# Pro_Micro_582V0_1.net
KiCad netlist of a schematic drawn in Altium Designer
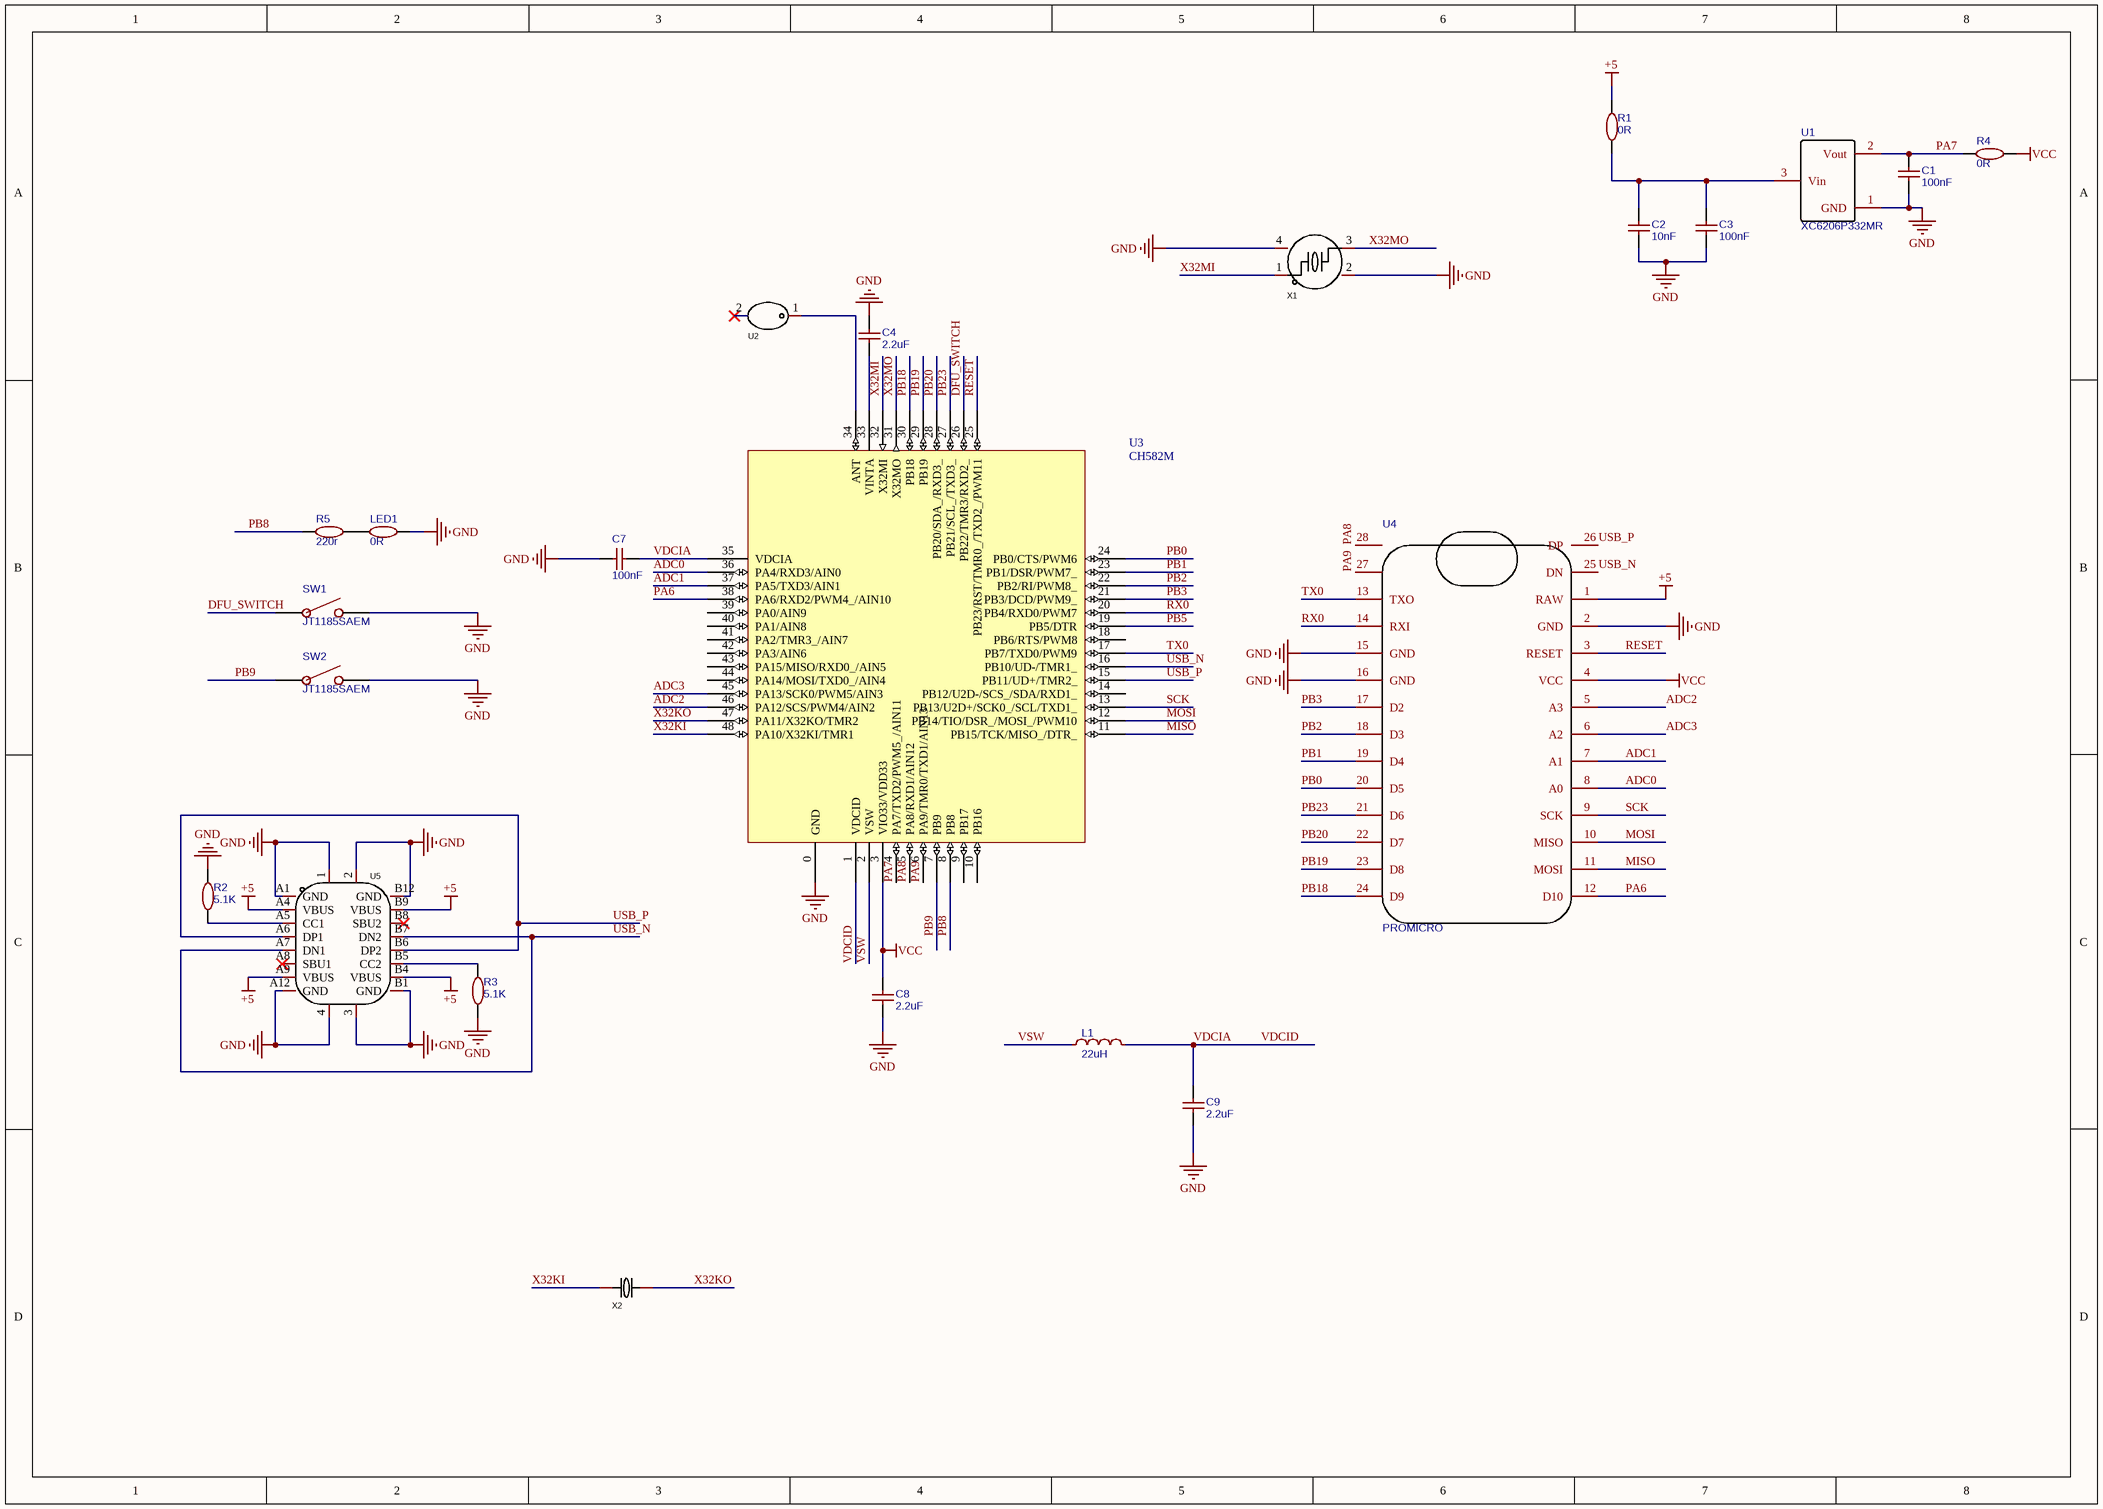
[diagram p0: Pro_Micro_582V0.1.SchDoc]

(export (version "E")
  (design (tool "Eeschema 10.0.6"))
  (components
    (comp (ref "C1")
      (value "100nF")
      (footprint "C0402")
      (fields
        (field (name "BOM_MANUFACTURER PART") "CC0805KKX5R6BB106")
        (field (name "BOM_SUPPLIER PART") "C89832")
      )
      (libsource (lib "CH582M") (part "电容"))
    )
    (comp (ref "C2")
      (value "10nF")
      (footprint "C0402")
      (fields
        (field (name "BOM_MANUFACTURER PART") "CC0805KKX5R6BB106")
        (field (name "BOM_SUPPLIER PART") "C89832")
      )
      (libsource (lib "CH582M") (part "电容"))
    )
    (comp (ref "C3")
      (value "100nF")
      (footprint "C0402")
      (fields
        (field (name "BOM_MANUFACTURER PART") "CC0805KKX5R6BB106")
        (field (name "BOM_SUPPLIER PART") "C89832")
      )
      (libsource (lib "CH582M") (part "电容"))
    )
    (comp (ref "C4")
      (value "2.2uF")
      (footprint "C0402")
      (fields
        (field (name "BOM_MANUFACTURER PART") "CC0805KKX5R6BB106")
        (field (name "BOM_SUPPLIER PART") "C89832")
      )
      (libsource (lib "CH582M") (part "电容"))
    )
    (comp (ref "C7")
      (value "100nF")
      (footprint "C0402")
      (fields
        (field (name "BOM_MANUFACTURER PART") "CC0805KKX5R6BB106")
        (field (name "BOM_SUPPLIER PART") "C89832")
      )
      (libsource (lib "CH582M") (part "电容"))
    )
    (comp (ref "C8")
      (value "2.2uF")
      (footprint "C0402")
      (fields
        (field (name "BOM_MANUFACTURER PART") "CC0805KKX5R6BB106")
        (field (name "BOM_SUPPLIER PART") "C89832")
      )
      (libsource (lib "CH582M") (part "电容"))
    )
    (comp (ref "C9")
      (value "2.2uF")
      (footprint "C0402")
      (fields
        (field (name "BOM_MANUFACTURER PART") "CC0805KKX5R6BB106")
        (field (name "BOM_SUPPLIER PART") "C89832")
      )
      (libsource (lib "CH582M") (part "电容"))
    )
    (comp (ref "L1")
      (value "22uH")
      (footprint "L0805")
      (fields
        (field (name "BOM_SUPPLIER PART") "C223184")
        (field (name "BOM_MANUFACTURER PART") "CBC2012T220K")
        (field (name "CONTRIBUTOR") "LCSC")
      )
      (libsource (lib "CH582M") (part "22uH"))
    )
    (comp (ref "LED1")
      (value "0R")
      (footprint "C0402")
      (fields
        (field (name "BOM_MANUFACTURER PART") "0603WAF1002T5E")
        (field (name "BOM_SUPPLIER PART") "C25804")
      )
      (libsource (lib "CH582M") (part "电阻"))
    )
    (comp (ref "R1")
      (value "0R")
      (footprint "R0402")
      (fields
        (field (name "BOM_MANUFACTURER PART") "0603WAF1002T5E")
        (field (name "BOM_SUPPLIER PART") "C25804")
      )
      (libsource (lib "CH582M") (part "电阻"))
    )
    (comp (ref "R2")
      (value "5.1K")
      (footprint "R0402")
      (fields
        (field (name "BOM_MANUFACTURER PART") "0603WAF1002T5E")
        (field (name "BOM_SUPPLIER PART") "C25804")
      )
      (libsource (lib "CH582M") (part "电阻"))
    )
    (comp (ref "R3")
      (value "5.1K")
      (footprint "R0402")
      (fields
        (field (name "BOM_MANUFACTURER PART") "0603WAF1002T5E")
        (field (name "BOM_SUPPLIER PART") "C25804")
      )
      (libsource (lib "CH582M") (part "电阻"))
    )
    (comp (ref "R4")
      (value "0R")
      (footprint "R0402")
      (fields
        (field (name "BOM_MANUFACTURER PART") "0603WAF1002T5E")
        (field (name "BOM_SUPPLIER PART") "C25804")
      )
      (libsource (lib "CH582M") (part "电阻"))
    )
    (comp (ref "R5")
      (value "220r")
      (footprint "C0402")
      (fields
        (field (name "BOM_MANUFACTURER PART") "0603WAF1002T5E")
        (field (name "BOM_SUPPLIER PART") "C25804")
      )
      (libsource (lib "CH582M") (part "电阻"))
    )
    (comp (ref "SW1")
      (value "JT1185SAEM")
      (footprint "SW-SMD_L3.9-W2.9-P4.15-LS5.0")
      (fields (field (name "BOM_SUPPLIER PART") "C465068") (field (name "CONTRIBUTOR") "LCSC"))
      (libsource (lib "CH582M") (part "JT1185SAEM"))
    )
    (comp (ref "SW2")
      (value "JT1185SAEM")
      (footprint "SW-SMD_L3.9-W2.9-P4.15-LS5.0")
      (fields (field (name "BOM_SUPPLIER PART") "C465068") (field (name "CONTRIBUTOR") "LCSC"))
      (libsource (lib "CH582M") (part "JT1185SAEM"))
    )
    (comp (ref "U1")
      (value "XC6206P332MR")
      (footprint "SOT-23-3_L2.9-W1.6-P1.90-LS2.8-BR")
      (fields (field (name "BOM_SUPPLIER PART") "C5446"))
      (libsource (lib "M2参考") (part "XC6206P332MR"))
    )
    (comp (ref "U2")
      (value "RFANT3216120A5T")
      (footprint "FILTER-SMD_1206-2P-L3.2-W1.6-L")
      (fields (field (name "MANUFACTURER") "Walsin(华新科)"))
      (libsource (lib "CH582M") (part "RFANT3216120A5T"))
    )
    (comp (ref "U3")
      (value "CH582M")
      (footprint "QFN48_5X5")
      (description "RISC-V MCU with BLE/2*USB/ADC/PWM/SPI/I2C/4*UART")
      (libsource (lib "CHXXX") (part "CH582M"))
    )
    (comp (ref "U4")
      (value "PROMICRO")
      (footprint "PROMICRO邮票孔")
      (fields (field (name "CONTRIBUTOR") "KongC"))
      (libsource (lib "Pro_Micro_CH582M") (part "PROMICRO"))
    )
    (comp (ref "U5")
      (value "20009-UCAF001-X")
      (footprint "TYPE-C-SMD_20009-UCAF001-X")
      (fields (field (name "MANUFACTURER") "MINTRON(明硕)"))
      (libsource (lib "CH582M") (part "20009-UCAF001-X"))
    )
    (comp (ref "X1")
      (value "X201632MOB4SI")
      (footprint "CRYSTAL-SMD_4P-L2.0-W1.6-BL-2")
      (fields (field (name "MANUFACTURER") "YXC(扬兴晶振)"))
      (libsource (lib "CH582M") (part "X201632MOB4SI"))
    )
    (comp (ref "X2")
      (value "SC-32S32.768kHz20PPM12.5pF")
      (footprint "OSC-SMD_L3.2-W1.5")
      (fields (field (name "MANUFACTURER") "Seiko(精工)"))
      (libsource (lib "CH582M") (part "SC-32S32.768kHz20PPM12.5pF"))
    )
  )
  (nets
    (net (code "1") (name "+5") (class "Default")
      (node (ref "R1") (pin "2") (pinfunction "2_2") (pintype "passive"))
      (node (ref "U4") (pin "1") (pinfunction "RAW_1") (pintype "passive"))
      (node (ref "U5") (pin "A4") (pinfunction "VBUS_A4") (pintype "passive"))
      (node (ref "U5") (pin "A9") (pinfunction "VBUS_A9") (pintype "passive"))
      (node (ref "U5") (pin "B4") (pinfunction "VBUS_B4") (pintype "passive"))
      (node (ref "U5") (pin "B9") (pinfunction "VBUS_B9") (pintype "passive"))
    )
    (net (code "2") (name "/ADC0") (class "Default")
      (node (ref "U3") (pin "36") (pinfunction "PA4/RXD3/AIN0_36") (pintype "bidirectional"))
      (node (ref "U4") (pin "8") (pinfunction "A0_8") (pintype "passive"))
    )
    (net (code "3") (name "/ADC1") (class "Default")
      (node (ref "U3") (pin "37") (pinfunction "PA5/TXD3/AIN1_37") (pintype "bidirectional"))
      (node (ref "U4") (pin "7") (pinfunction "A1_7") (pintype "passive"))
    )
    (net (code "4") (name "/ADC2") (class "Default")
      (node (ref "U3") (pin "46") (pinfunction "PA12/SCS/PWM4/AIN2_46") (pintype "bidirectional"))
      (node (ref "U4") (pin "5") (pinfunction "A3_5") (pintype "passive"))
    )
    (net (code "5") (name "/ADC3") (class "Default")
      (node (ref "U3") (pin "45") (pinfunction "PA13/SCK0/PWM5/AIN3_45") (pintype "bidirectional"))
      (node (ref "U4") (pin "6") (pinfunction "A2_6") (pintype "passive"))
    )
    (net (code "6") (name "/DFU_SWITCH") (class "Default")
      (node (ref "SW1") (pin "1") (pinfunction "1_1") (pintype "passive"))
      (node (ref "U3") (pin "26") (pinfunction "PB22/TMR3/RXD2__26") (pintype "bidirectional"))
    )
    (net (code "7") (name "/MISO") (class "Default")
      (node (ref "U3") (pin "11") (pinfunction "PB15/TCK/MISO_/DTR__11") (pintype "bidirectional"))
      (node (ref "U4") (pin "11") (pinfunction "MOSI_11") (pintype "passive"))
    )
    (net (code "8") (name "/MOSI") (class "Default")
      (node (ref "U3") (pin "12") (pinfunction "PB14/TIO/DSR_/MOSI_/PWM10_12") (pintype "bidirectional"))
      (node (ref "U4") (pin "10") (pinfunction "MISO_10") (pintype "passive"))
    )
    (net (code "9") (name "/PA6") (class "Default")
      (node (ref "U3") (pin "38") (pinfunction "PA6/RXD2/PWM4_/AIN10_38") (pintype "bidirectional"))
      (node (ref "U4") (pin "12") (pinfunction "D10_12") (pintype "passive"))
    )
    (net (code "10") (name "/PA7") (class "Default")
      (node (ref "C1") (pin "2") (pinfunction "2_2") (pintype "passive"))
      (node (ref "R4") (pin "2") (pinfunction "2_2") (pintype "passive"))
      (node (ref "U1") (pin "2") (pinfunction "Vout_2") (pintype "passive"))
      (node (ref "U3") (pin "4") (pinfunction "PA7/TXD2/PWM5_/AIN11_4") (pintype "bidirectional"))
    )
    (net (code "11") (name "/PA8") (class "Default")
      (node (ref "U3") (pin "5") (pinfunction "PA8/RXD1/AIN12_5") (pintype "bidirectional"))
      (node (ref "U4") (pin "28") (pintype "passive"))
    )
    (net (code "12") (name "/PA9") (class "Default")
      (node (ref "U3") (pin "6") (pinfunction "PA9/TMR0/TXD1/AIN13_6") (pintype "bidirectional"))
      (node (ref "U4") (pin "27") (pintype "passive"))
    )
    (net (code "13") (name "/PB0") (class "Default")
      (node (ref "U3") (pin "24") (pinfunction "PB0/CTS/PWM6_24") (pintype "bidirectional"))
      (node (ref "U4") (pin "20") (pinfunction "D5_20") (pintype "passive"))
    )
    (net (code "14") (name "/PB1") (class "Default")
      (node (ref "U3") (pin "23") (pinfunction "PB1/DSR/PWM7__23") (pintype "bidirectional"))
      (node (ref "U4") (pin "19") (pinfunction "D4_19") (pintype "passive"))
    )
    (net (code "15") (name "/PB2") (class "Default")
      (node (ref "U3") (pin "22") (pinfunction "PB2/RI/PWM8__22") (pintype "bidirectional"))
      (node (ref "U4") (pin "18") (pinfunction "D3_18") (pintype "passive"))
    )
    (net (code "16") (name "/PB3") (class "Default")
      (node (ref "U3") (pin "21") (pinfunction "PB3/DCD/PWM9__21") (pintype "bidirectional"))
      (node (ref "U4") (pin "17") (pinfunction "D2_17") (pintype "passive"))
    )
    (net (code "17") (name "/PB5") (class "Default")
      (node (ref "U3") (pin "19") (pinfunction "PB5/DTR_19") (pintype "bidirectional"))
    )
    (net (code "18") (name "/PB8") (class "Default")
      (node (ref "R5") (pin "1") (pinfunction "1_1") (pintype "passive"))
      (node (ref "U3") (pin "8") (pinfunction "PB8_8") (pintype "bidirectional"))
    )
    (net (code "19") (name "/PB9") (class "Default")
      (node (ref "SW2") (pin "1") (pinfunction "1_1") (pintype "passive"))
      (node (ref "U3") (pin "7") (pinfunction "PB9_7") (pintype "bidirectional"))
    )
    (net (code "20") (name "/PB18") (class "Default")
      (node (ref "U3") (pin "30") (pinfunction "PB18_30") (pintype "bidirectional"))
      (node (ref "U4") (pin "24") (pinfunction "D9_24") (pintype "passive"))
    )
    (net (code "21") (name "/PB19") (class "Default")
      (node (ref "U3") (pin "29") (pinfunction "PB19_29") (pintype "bidirectional"))
      (node (ref "U4") (pin "23") (pinfunction "D8_23") (pintype "passive"))
    )
    (net (code "22") (name "/PB20") (class "Default")
      (node (ref "U3") (pin "28") (pinfunction "PB20/SDA_/RXD3__28") (pintype "bidirectional"))
      (node (ref "U4") (pin "22") (pinfunction "D7_22") (pintype "passive"))
    )
    (net (code "23") (name "/PB23") (class "Default")
      (node (ref "U3") (pin "27") (pinfunction "PB21/SCL_/TXD3__27") (pintype "bidirectional"))
      (node (ref "U4") (pin "21") (pinfunction "D6_21") (pintype "passive"))
    )
    (net (code "24") (name "/RESET") (class "Default")
      (node (ref "U3") (pin "25") (pinfunction "PB23/RST/TMR0_/TXD2_/PWM11_25") (pintype "bidirectional"))
      (node (ref "U4") (pin "3") (pinfunction "RESET_3") (pintype "passive"))
    )
    (net (code "25") (name "/RX0") (class "Default")
      (node (ref "U3") (pin "20") (pinfunction "PB4/RXD0/PWM7_20") (pintype "bidirectional"))
      (node (ref "U4") (pin "14") (pinfunction "RXI_14") (pintype "passive"))
    )
    (net (code "26") (name "/SCK") (class "Default")
      (node (ref "U3") (pin "13") (pinfunction "PB13/U2D+/SCK0_/SCL/TXD1__13") (pintype "bidirectional"))
      (node (ref "U4") (pin "9") (pinfunction "SCK_9") (pintype "passive"))
    )
    (net (code "27") (name "/TX0") (class "Default")
      (node (ref "U3") (pin "17") (pinfunction "PB7/TXD0/PWM9_17") (pintype "bidirectional"))
      (node (ref "U4") (pin "13") (pinfunction "TXO_13") (pintype "passive"))
    )
    (net (code "28") (name "/USB_N") (class "Default")
      (node (ref "U3") (pin "16") (pinfunction "PB10/UD-/TMR1__16") (pintype "bidirectional"))
      (node (ref "U4") (pin "25") (pinfunction "DN_25") (pintype "passive"))
      (node (ref "U5") (pin "A7") (pinfunction "DN1_A7") (pintype "passive"))
      (node (ref "U5") (pin "B7") (pinfunction "DN2_B7") (pintype "passive"))
    )
    (net (code "29") (name "/USB_P") (class "Default")
      (node (ref "U3") (pin "15") (pinfunction "PB11/UD+/TMR2__15") (pintype "bidirectional"))
      (node (ref "U4") (pin "26") (pinfunction "DP_26") (pintype "passive"))
      (node (ref "U5") (pin "A6") (pinfunction "DP1_A6") (pintype "passive"))
      (node (ref "U5") (pin "B6") (pinfunction "DP2_B6") (pintype "passive"))
    )
    (net (code "30") (name "/VDCIA") (class "Default")
      (node (ref "C7") (pin "1") (pinfunction "1_1") (pintype "passive"))
      (node (ref "C9") (pin "2") (pinfunction "2_2") (pintype "passive"))
      (node (ref "L1") (pin "2") (pinfunction "2_2") (pintype "passive"))
      (node (ref "U3") (pin "1") (pinfunction "VDCID_1") (pintype "power_in"))
      (node (ref "U3") (pin "35") (pinfunction "VDCIA_35") (pintype "power_in"))
    )
    (net (code "31") (name "/VSW") (class "Default")
      (node (ref "L1") (pin "1") (pinfunction "1_1") (pintype "passive"))
      (node (ref "U3") (pin "2") (pinfunction "VSW_2") (pintype "power_in"))
    )
    (net (code "32") (name "/X32KI") (class "Default")
      (node (ref "U3") (pin "48") (pinfunction "PA10/X32KI/TMR1_48") (pintype "bidirectional"))
      (node (ref "X2") (pin "1") (pinfunction "1_1") (pintype "passive"))
    )
    (net (code "33") (name "/X32KO") (class "Default")
      (node (ref "U3") (pin "47") (pinfunction "PA11/X32KO/TMR2_47") (pintype "bidirectional"))
      (node (ref "X2") (pin "2") (pinfunction "2_2") (pintype "passive"))
    )
    (net (code "34") (name "/X32MI") (class "Default")
      (node (ref "U3") (pin "32") (pinfunction "X32MI_32") (pintype "input"))
      (node (ref "X1") (pin "1") (pinfunction "1_1") (pintype "passive"))
    )
    (net (code "35") (name "/X32MO") (class "Default")
      (node (ref "U3") (pin "31") (pinfunction "X32MO_31") (pintype "output"))
      (node (ref "X1") (pin "3") (pinfunction "3_3") (pintype "passive"))
    )
    (net (code "36") (name "GND") (class "Default")
      (node (ref "C1") (pin "1") (pinfunction "1_1") (pintype "passive"))
      (node (ref "C2") (pin "1") (pinfunction "1_1") (pintype "passive"))
      (node (ref "C3") (pin "1") (pinfunction "1_1") (pintype "passive"))
      (node (ref "C4") (pin "2") (pinfunction "2_2") (pintype "passive"))
      (node (ref "C7") (pin "2") (pinfunction "2_2") (pintype "passive"))
      (node (ref "C8") (pin "1") (pinfunction "1_1") (pintype "passive"))
      (node (ref "C9") (pin "1") (pinfunction "1_1") (pintype "passive"))
      (node (ref "LED1") (pin "1") (pinfunction "1_1") (pintype "passive"))
      (node (ref "R2") (pin "2") (pinfunction "2_2") (pintype "passive"))
      (node (ref "R3") (pin "2") (pinfunction "2_2") (pintype "passive"))
      (node (ref "SW1") (pin "2") (pinfunction "2_2") (pintype "passive"))
      (node (ref "SW2") (pin "2") (pinfunction "2_2") (pintype "passive"))
      (node (ref "U1") (pin "1") (pinfunction "GND_1") (pintype "passive"))
      (node (ref "U3") (pin "0") (pinfunction "GND_0") (pintype "power_in"))
      (node (ref "U4") (pin "15") (pinfunction "GND_15") (pintype "passive"))
      (node (ref "U4") (pin "16") (pinfunction "GND_16") (pintype "passive"))
      (node (ref "U4") (pin "2") (pinfunction "GND_2") (pintype "passive"))
      (node (ref "U5") (pin "1") (pinfunction "1_1") (pintype "passive"))
      (node (ref "U5") (pin "2") (pinfunction "2_2") (pintype "passive"))
      (node (ref "U5") (pin "3") (pinfunction "3_3") (pintype "passive"))
      (node (ref "U5") (pin "4") (pinfunction "4_4") (pintype "passive"))
      (node (ref "U5") (pin "A1") (pinfunction "GND_A1") (pintype "passive"))
      (node (ref "U5") (pin "A12") (pinfunction "GND_A12") (pintype "passive"))
      (node (ref "U5") (pin "B1") (pinfunction "GND_B1") (pintype "passive"))
      (node (ref "U5") (pin "B12") (pinfunction "GND_B12") (pintype "passive"))
      (node (ref "X1") (pin "2") (pinfunction "GND_2") (pintype "passive"))
      (node (ref "X1") (pin "4") (pinfunction "GND_4") (pintype "passive"))
    )
    (net (code "37") (name "Net-(LED1-Pad2)") (class "Default")
      (node (ref "LED1") (pin "2") (pinfunction "2_2") (pintype "passive"))
      (node (ref "R5") (pin "2") (pinfunction "2_2") (pintype "passive"))
    )
    (net (code "38") (name "Net-(U1-Vin)") (class "Default")
      (node (ref "C2") (pin "2") (pinfunction "2_2") (pintype "passive"))
      (node (ref "C3") (pin "2") (pinfunction "2_2") (pintype "passive"))
      (node (ref "R1") (pin "1") (pinfunction "1_1") (pintype "passive"))
      (node (ref "U1") (pin "3") (pinfunction "Vin_3") (pintype "passive"))
    )
    (net (code "39") (name "Net-(U3-ANT)") (class "Default")
      (node (ref "U2") (pin "1") (pinfunction "1_1") (pintype "passive"))
      (node (ref "U3") (pin "34") (pinfunction "ANT_34") (pintype "bidirectional"))
    )
    (net (code "40") (name "Net-(U3-VINTA)") (class "Default")
      (node (ref "C4") (pin "1") (pinfunction "1_1") (pintype "passive"))
      (node (ref "U3") (pin "33") (pinfunction "VINTA_33") (pintype "power_in"))
    )
    (net (code "41") (name "Net-(U5-CC1)") (class "Default")
      (node (ref "R2") (pin "1") (pinfunction "1_1") (pintype "passive"))
      (node (ref "U5") (pin "A5") (pinfunction "CC1_A5") (pintype "passive"))
    )
    (net (code "42") (name "Net-(U5-CC2)") (class "Default")
      (node (ref "R3") (pin "1") (pinfunction "1_1") (pintype "passive"))
      (node (ref "U5") (pin "B5") (pinfunction "CC2_B5") (pintype "passive"))
    )
    (net (code "43") (name "VCC") (class "Default")
      (node (ref "C8") (pin "2") (pinfunction "2_2") (pintype "passive"))
      (node (ref "R4") (pin "1") (pinfunction "1_1") (pintype "passive"))
      (node (ref "U3") (pin "3") (pinfunction "VIO33/VDD33_3") (pintype "power_in"))
      (node (ref "U4") (pin "4") (pinfunction "VCC_4") (pintype "passive"))
    )
    (net (code "44") (name "unconnected-(U2-Pad2)") (class "Default")
      (node (ref "U2") (pin "2") (pinfunction "2_2") (pintype "passive+no_connect"))
    )
    (net (code "45") (name "unconnected-(U3-PA0{slash}AIN9-Pad39)") (class "Default")
      (node (ref "U3") (pin "39") (pinfunction "PA0/AIN9_39") (pintype "bidirectional"))
    )
    (net (code "46") (name "unconnected-(U3-PA1{slash}AIN8-Pad40)") (class "Default")
      (node (ref "U3") (pin "40") (pinfunction "PA1/AIN8_40") (pintype "bidirectional"))
    )
    (net (code "47") (name "unconnected-(U3-PA2{slash}TMR3_{slash}AIN7-Pad41)") (class "Default")
      (node (ref "U3") (pin "41") (pinfunction "PA2/TMR3_/AIN7_41") (pintype "bidirectional"))
    )
    (net (code "48") (name "unconnected-(U3-PA3{slash}AIN6-Pad42)") (class "Default")
      (node (ref "U3") (pin "42") (pinfunction "PA3/AIN6_42") (pintype "bidirectional"))
    )
    (net (code "49") (name "unconnected-(U3-PA14{slash}MOSI{slash}TXD0_{slash}AIN4-Pad44)") (class "Default")
      (node (ref "U3") (pin "44") (pinfunction "PA14/MOSI/TXD0_/AIN4_44") (pintype "bidirectional"))
    )
    (net (code "50") (name "unconnected-(U3-PA15{slash}MISO{slash}RXD0_{slash}AIN5-Pad43)") (class "Default")
      (node (ref "U3") (pin "43") (pinfunction "PA15/MISO/RXD0_/AIN5_43") (pintype "bidirectional"))
    )
    (net (code "51") (name "unconnected-(U3-PB6{slash}RTS{slash}PWM8-Pad18)") (class "Default")
      (node (ref "U3") (pin "18") (pinfunction "PB6/RTS/PWM8_18") (pintype "bidirectional"))
    )
    (net (code "52") (name "unconnected-(U3-PB12{slash}U2D-{slash}SCS_{slash}SDA{slash}RXD1_-Pad14)") (class "Default")
      (node (ref "U3") (pin "14") (pinfunction "PB12/U2D-/SCS_/SDA/RXD1__14") (pintype "bidirectional"))
    )
    (net (code "53") (name "unconnected-(U3-PB16-Pad10)") (class "Default")
      (node (ref "U3") (pin "10") (pinfunction "PB16_10") (pintype "bidirectional"))
    )
    (net (code "54") (name "unconnected-(U3-PB17-Pad9)") (class "Default")
      (node (ref "U3") (pin "9") (pinfunction "PB17_9") (pintype "bidirectional"))
    )
    (net (code "55") (name "unconnected-(U5-SBU1-PadA8)") (class "Default")
      (node (ref "U5") (pin "A8") (pinfunction "SBU1_A8") (pintype "passive+no_connect"))
    )
    (net (code "56") (name "unconnected-(U5-SBU2-PadB8)") (class "Default")
      (node (ref "U5") (pin "B8") (pinfunction "SBU2_B8") (pintype "passive+no_connect"))
    )
  )
)
